# inktime_schematic.net
KiCad netlist of a schematic drawn in EAGLE
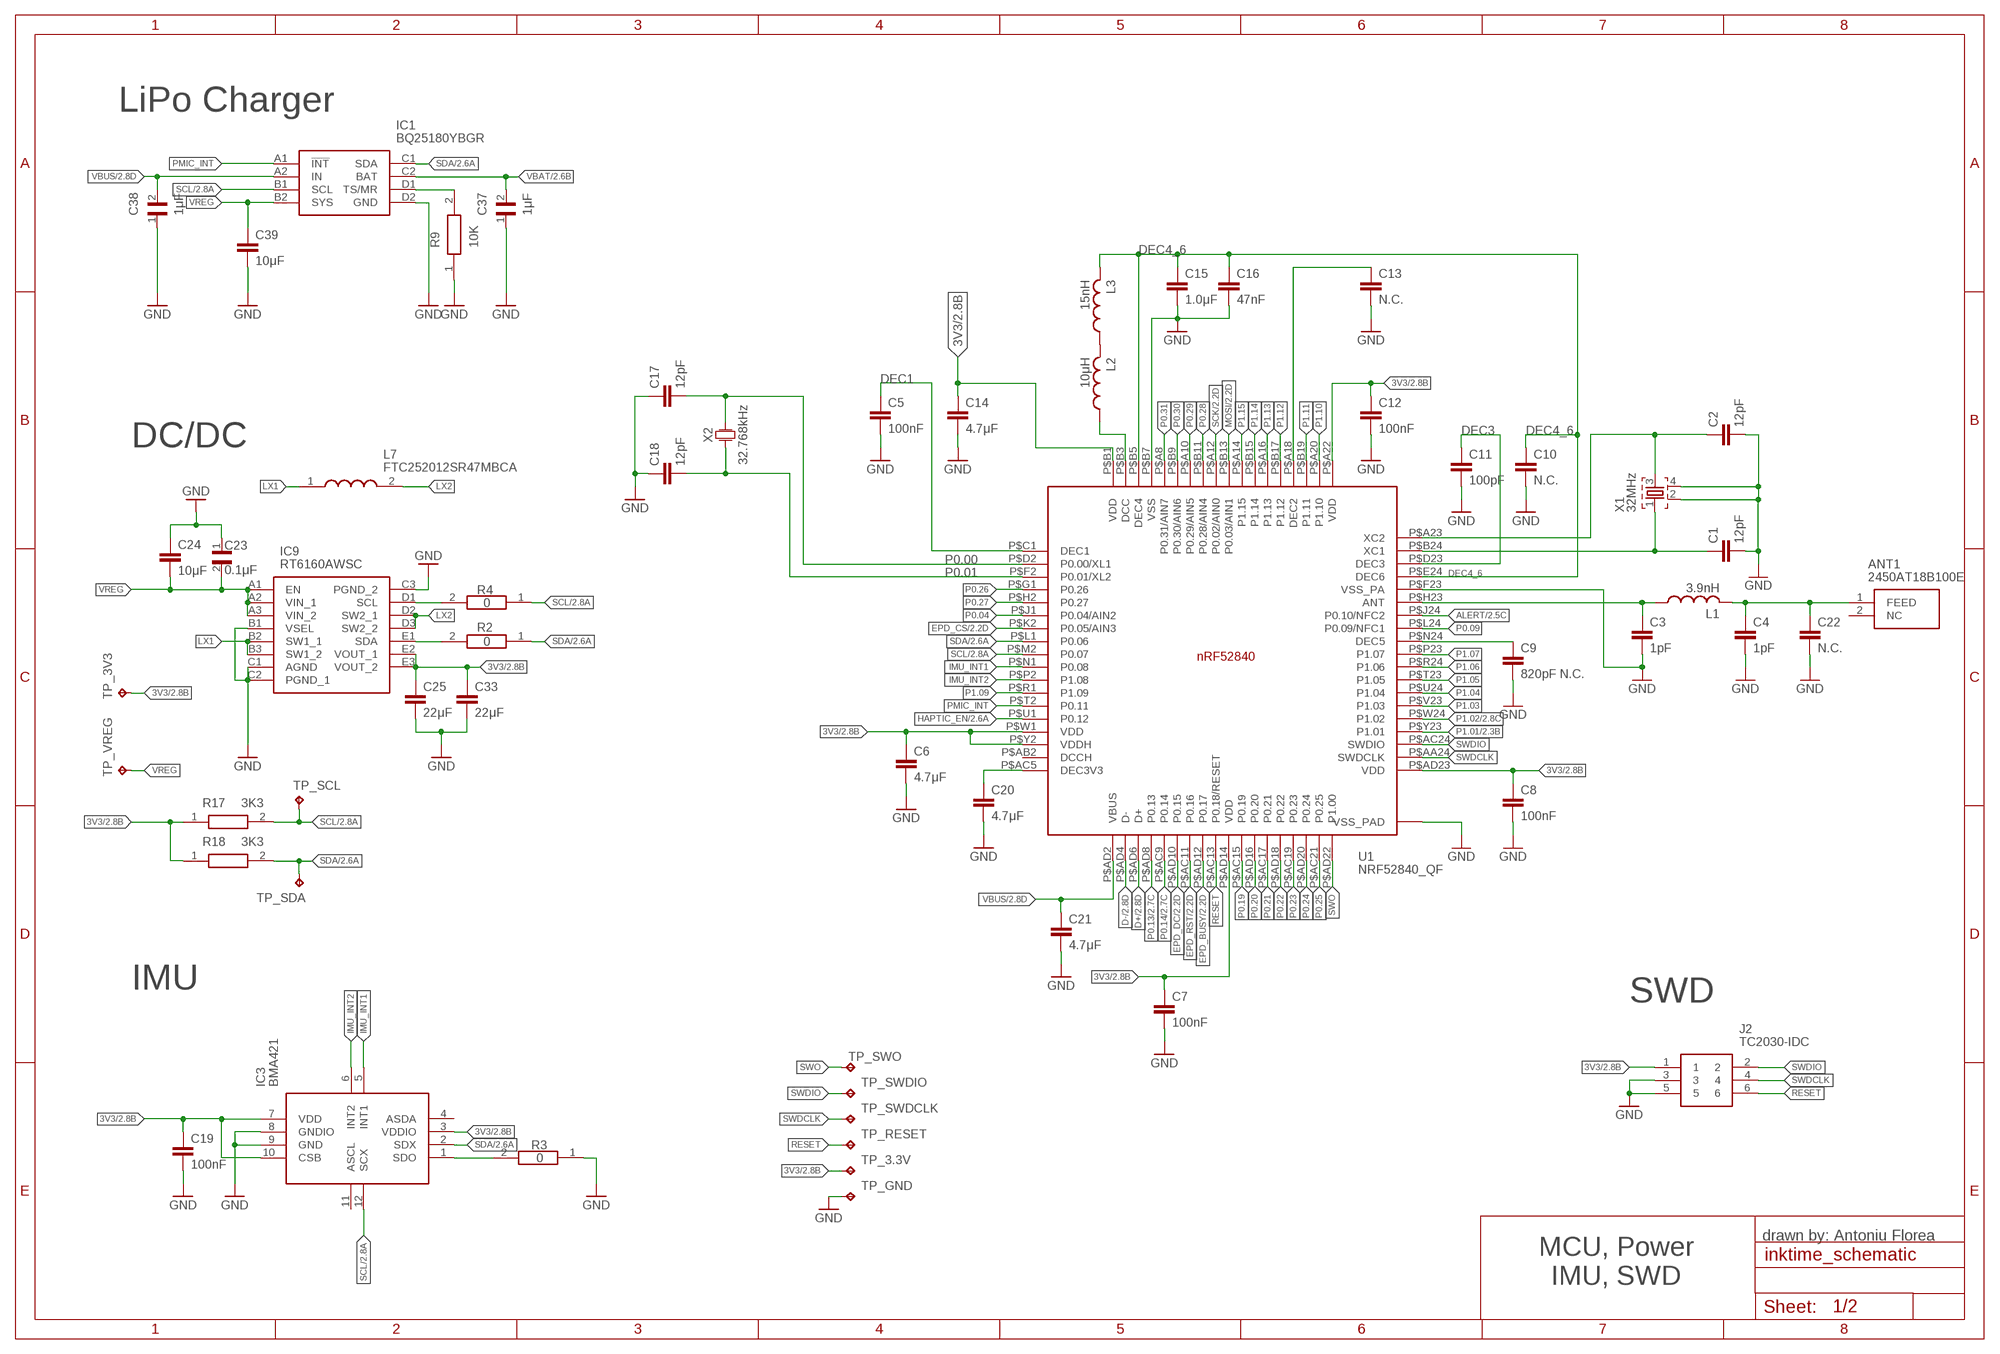
[diagram p0: schematic, sheet 1]
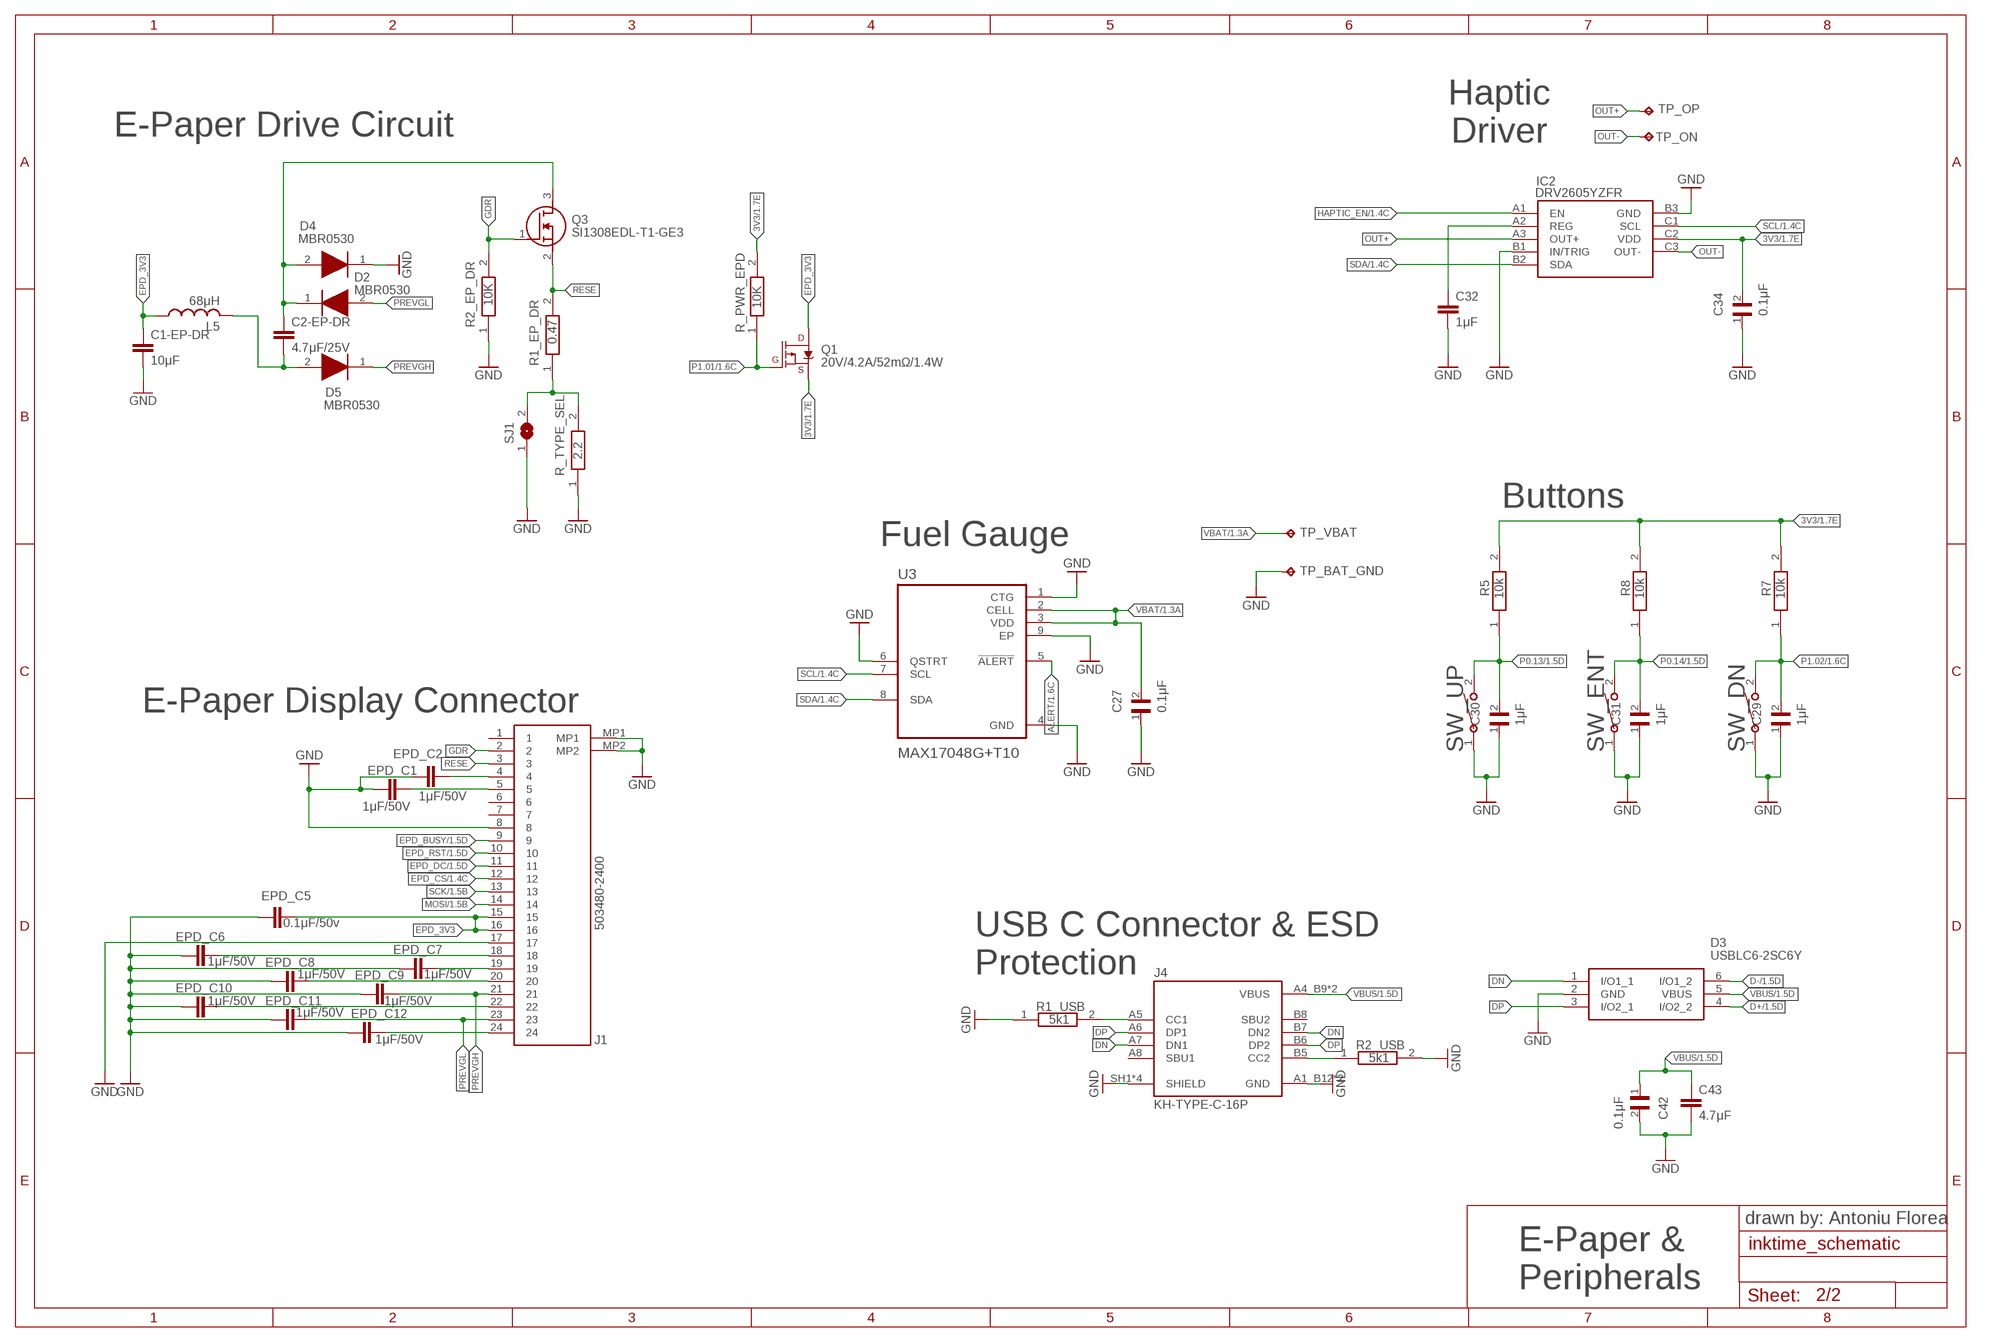
[diagram p1: schematic, sheet 2]

(export (version "E")
  (design (tool "Eeschema 10.0.6"))
  (components
    (comp (ref "C1-EP-DR")
      (value "10μF")
      (footprint "eagle-import:NORDIC_NRF_3_RESC0402_L")
      (libsource (lib "eagle-import") (part "NORDIC_NRF_3_CAPACITOR_0402_L"))
    )
    (comp (ref "C2-EP-DR")
      (value "4.7μF/25V")
      (footprint "eagle-import:NORDIC_NRF_3_RESC0402_L")
      (libsource (lib "eagle-import") (part "NORDIC_NRF_3_CAPACITOR_0402_L"))
    )
    (comp (ref "C27")
      (value "0.1μF")
      (footprint "eagle-import:GRM011R60J152KE01L_2_CAPC0201X13N")
      (fields (field (name "MF") "Murata") (field (name "MP") "GRM011R60J152KE01L"))
      (libsource (lib "eagle-import") (part "GRM011R60J152KE01L_2_GRM011R60J152KE01L"))
    )
    (comp (ref "C29")
      (value "1μF")
      (footprint "eagle-import:GRM011R60J152KE01L_2_CAPC0201X13N")
      (fields (field (name "MF") "Murata") (field (name "MP") "GRM011R60J152KE01L"))
      (libsource (lib "eagle-import") (part "GRM011R60J152KE01L_2_GRM011R60J152KE01L"))
    )
    (comp (ref "C30")
      (value "1μF")
      (footprint "eagle-import:GRM011R60J152KE01L_2_CAPC0201X13N")
      (fields (field (name "MF") "Murata") (field (name "MP") "GRM011R60J152KE01L"))
      (libsource (lib "eagle-import") (part "GRM011R60J152KE01L_2_GRM011R60J152KE01L"))
    )
    (comp (ref "C31")
      (value "1μF")
      (footprint "eagle-import:GRM011R60J152KE01L_2_CAPC0201X13N")
      (fields (field (name "MF") "Murata") (field (name "MP") "GRM011R60J152KE01L"))
      (libsource (lib "eagle-import") (part "GRM011R60J152KE01L_2_GRM011R60J152KE01L"))
    )
    (comp (ref "C32")
      (value "1μF")
      (footprint "eagle-import:NORDIC_NRF_3_RESC0402_L")
      (libsource (lib "eagle-import") (part "NORDIC_NRF_3_CAPACITOR_0402_L"))
    )
    (comp (ref "C34")
      (value "0.1μF")
      (footprint "eagle-import:GRM011R60J152KE01L_2_CAPC0201X13N")
      (fields (field (name "MF") "Murata") (field (name "MP") "GRM011R60J152KE01L"))
      (libsource (lib "eagle-import") (part "GRM011R60J152KE01L_2_GRM011R60J152KE01L"))
    )
    (comp (ref "C42")
      (value "0.1μF")
      (footprint "eagle-import:GRM011R60J152KE01L_2_CAPC0201X13N")
      (fields (field (name "MF") "Murata") (field (name "MP") "GRM011R60J152KE01L"))
      (libsource (lib "eagle-import") (part "GRM011R60J152KE01L_2_GRM011R60J152KE01L"))
    )
    (comp (ref "C43")
      (value "4.7μF")
      (footprint "eagle-import:NORDIC_NRF_3_RESC0402_L")
      (libsource (lib "eagle-import") (part "NORDIC_NRF_3_CAPACITOR_0402_L"))
    )
    (comp (ref "D2")
      (value "MBR0530")
      (footprint "eagle-import:ESP32_C6_LIBRARY_5_SOD3716X135N")
      (fields (field (name "MF") "ON Semiconductor"))
      (libsource (lib "eagle-import") (part "ESP32_C6_LIBRARY_5_MBR0530"))
    )
    (comp (ref "D3")
      (value "USBLC6-2SC6Y")
      (footprint "eagle-import:ESP32_C6_LIBRARY_3_SOT95P280X145-6N")
      (fields (field (name "MF") "STMicroelectronics"))
      (libsource (lib "eagle-import") (part "ESP32_C6_LIBRARY_3_USBLC6-2SC6Y"))
    )
    (comp (ref "D4")
      (value "MBR0530")
      (footprint "eagle-import:ESP32_C6_LIBRARY_5_SOD3716X135N")
      (fields (field (name "MF") "ON Semiconductor"))
      (libsource (lib "eagle-import") (part "ESP32_C6_LIBRARY_5_MBR0530"))
    )
    (comp (ref "D5")
      (value "MBR0530")
      (footprint "eagle-import:ESP32_C6_LIBRARY_5_SOD3716X135N")
      (fields (field (name "MF") "ON Semiconductor"))
      (libsource (lib "eagle-import") (part "ESP32_C6_LIBRARY_5_MBR0530"))
    )
    (comp (ref "EPD_C1")
      (value "1μF/50V")
      (footprint "eagle-import:NORDIC_NRF_3_RESC0402_L")
      (libsource (lib "eagle-import") (part "NORDIC_NRF_3_CAPACITOR_0402_L"))
    )
    (comp (ref "EPD_C2")
      (value "1μF/50V")
      (footprint "eagle-import:NORDIC_NRF_3_RESC0402_L")
      (libsource (lib "eagle-import") (part "NORDIC_NRF_3_CAPACITOR_0402_L"))
    )
    (comp (ref "EPD_C5")
      (value "0.1μF/50v")
      (footprint "eagle-import:NORDIC_NRF_3_RESC0201_L")
      (libsource (lib "eagle-import") (part "NORDIC_NRF_3_CAPACITOR_0201_L"))
    )
    (comp (ref "EPD_C6")
      (value "1μF/50V")
      (footprint "eagle-import:NORDIC_NRF_3_RESC0402_L")
      (libsource (lib "eagle-import") (part "NORDIC_NRF_3_CAPACITOR_0402_L"))
    )
    (comp (ref "EPD_C7")
      (value "1μF/50V")
      (footprint "eagle-import:NORDIC_NRF_3_RESC0402_L")
      (libsource (lib "eagle-import") (part "NORDIC_NRF_3_CAPACITOR_0402_L"))
    )
    (comp (ref "EPD_C8")
      (value "1μF/50V")
      (footprint "eagle-import:NORDIC_NRF_3_RESC0402_L")
      (libsource (lib "eagle-import") (part "NORDIC_NRF_3_CAPACITOR_0402_L"))
    )
    (comp (ref "EPD_C9")
      (value "1μF/50V")
      (footprint "eagle-import:NORDIC_NRF_3_RESC0402_L")
      (libsource (lib "eagle-import") (part "NORDIC_NRF_3_CAPACITOR_0402_L"))
    )
    (comp (ref "EPD_C10")
      (value "1μF/50V")
      (footprint "eagle-import:NORDIC_NRF_3_RESC0402_L")
      (libsource (lib "eagle-import") (part "NORDIC_NRF_3_CAPACITOR_0402_L"))
    )
    (comp (ref "EPD_C11")
      (value "1μF/50V")
      (footprint "eagle-import:NORDIC_NRF_3_RESC0402_L")
      (libsource (lib "eagle-import") (part "NORDIC_NRF_3_CAPACITOR_0402_L"))
    )
    (comp (ref "EPD_C12")
      (value "1μF/50V")
      (footprint "eagle-import:NORDIC_NRF_3_RESC0402_L")
      (libsource (lib "eagle-import") (part "NORDIC_NRF_3_CAPACITOR_0402_L"))
    )
    (comp (ref "IC2")
      (value "DRV2605YZFR")
      (footprint "eagle-import:DRV2605YZFR_BGA9C50P3X3_144X144X62")
      (libsource (lib "eagle-import") (part "DRV2605YZFR_DRV2605YZFR"))
    )
    (comp (ref "J1")
      (value "503480-2400")
      (footprint "eagle-import:503480-2400_5034802400")
      (fields (field (name "MOUSER_PART_NUMBER") "538-503480-2400"))
      (libsource (lib "eagle-import") (part "503480-2400_503480-2400"))
    )
    (comp (ref "J4")
      (value "KH-TYPE-C-16P")
      (footprint "eagle-import:KH-TYPE-C-16P_KINGHELM_KH-TYPE-C-16P")
      (fields (field (name "MF") "kinghelm"))
      (libsource (lib "eagle-import") (part "KH-TYPE-C-16P_KH-TYPE-C-16P"))
    )
    (comp (ref "L5")
      (value "68μH")
      (footprint "eagle-import:NORDIC_NRF_2_RESC0402_L")
      (libsource (lib "eagle-import") (part "NORDIC_NRF_2_INDUCTOR_0402_L"))
    )
    (comp (ref "Q1")
      (value "20V/4.2A/52mΩ/1.4W")
      (footprint "eagle-import:ESP32_C6_LIBRARY_4_ESP32_C6_LIBRARY_4_ESP32_C6_LIBRARY_4_ESP32_C6_LIBRARY_4_ESP32_WROVER_SPARKFUN-DISCRETESEMI_SOT23-3")
      (libsource (lib "eagle-import") (part "ESP32_C6_LIBRARY_4_ESP32_WROVER_SPARKFUN-DISCRETESEMI_MOSFET_PCH-DMG2305UX-7"))
    )
    (comp (ref "Q3")
      (value "SI1308EDL-T1-GE3")
      (footprint "eagle-import:ESP32_C6_LIBRARY_6_SOT65P210X110-3N")
      (fields (field (name "MF") "Vishay Siliconix"))
      (libsource (lib "eagle-import") (part "ESP32_C6_LIBRARY_6_SI1308EDL-T1-GE3"))
    )
    (comp (ref "R1_EP_DR")
      (value "0.47")
      (footprint "eagle-import:CPF0201D7K68C1_0201")
      (libsource (lib "eagle-import") (part "CPF0201D7K68C1_CPF0201D7K68C1"))
    )
    (comp (ref "R1_USB")
      (value "5k1")
      (footprint "eagle-import:ERA-1AEB3401C_0201")
      (libsource (lib "eagle-import") (part "ERA-1AEB3401C_CPF0201D7K68C1"))
    )
    (comp (ref "R2_EP_DR")
      (value "10K")
      (footprint "eagle-import:CPF0201D7K68C1_0201")
      (libsource (lib "eagle-import") (part "CPF0201D7K68C1_CPF0201D7K68C1"))
    )
    (comp (ref "R2_USB")
      (value "5k1")
      (footprint "eagle-import:ERA-1AEB3401C_0201")
      (libsource (lib "eagle-import") (part "ERA-1AEB3401C_CPF0201D7K68C1"))
    )
    (comp (ref "R5")
      (value "10k")
      (footprint "eagle-import:CPF0201D7K68C1_0201")
      (libsource (lib "eagle-import") (part "CPF0201D7K68C1_CPF0201D7K68C1"))
    )
    (comp (ref "R7")
      (value "10k")
      (footprint "eagle-import:CPF0201D7K68C1_0201")
      (libsource (lib "eagle-import") (part "CPF0201D7K68C1_CPF0201D7K68C1"))
    )
    (comp (ref "R8")
      (value "10k")
      (footprint "eagle-import:CPF0201D7K68C1_0201")
      (libsource (lib "eagle-import") (part "CPF0201D7K68C1_CPF0201D7K68C1"))
    )
    (comp (ref "R_PWR_EPD")
      (value "10K")
      (footprint "eagle-import:CPF0201D7K68C1_0201")
      (libsource (lib "eagle-import") (part "CPF0201D7K68C1_CPF0201D7K68C1"))
    )
    (comp (ref "R_TYPE_SEL")
      (value "2.2")
      (footprint "eagle-import:CPF0201D7K68C1_0201")
      (libsource (lib "eagle-import") (part "CPF0201D7K68C1_CPF0201D7K68C1"))
    )
    (comp (ref "SJ1")
      (value "ESP32_C6_LIBRARY_7_JUMPER_SJ")
      (footprint "eagle-import:ESP32_C6_LIBRARY_7_JUMPER_SJ")
      (libsource (lib "eagle-import") (part "ESP32_C6_LIBRARY_7_JUMPER_SJ"))
    )
    (comp (ref "SW_DN")
      (value "2025-10-22_07-23-44_LIBRARY_EVP-AKE31ASW_EVP-AKE31A_PAN")
      (footprint "eagle-import:2025-10-22_07-23-44_LIBRARY_SW_EVP-AKE31A_PAN")
      (fields
        (field (name "MANUFACTURER_PART_NUMBER") "EVP-AKE31A")
        (field (name "COPYRIGHT") "Copyright (C) 2025 Ultra Librarian. All rights reserved.")
      )
      (libsource (lib "eagle-import") (part "2025-10-22_07-23-44_LIBRARY_EVP-AKE31ASW_EVP-AKE31A_PAN"))
    )
    (comp (ref "SW_ENT")
      (value "2025-10-22_07-23-44_LIBRARY_EVP-AKE31ASW_EVP-AKE31A_PAN")
      (footprint "eagle-import:2025-10-22_07-23-44_LIBRARY_SW_EVP-AKE31A_PAN")
      (fields
        (field (name "MANUFACTURER_PART_NUMBER") "EVP-AKE31A")
        (field (name "COPYRIGHT") "Copyright (C) 2025 Ultra Librarian. All rights reserved.")
      )
      (libsource (lib "eagle-import") (part "2025-10-22_07-23-44_LIBRARY_EVP-AKE31ASW_EVP-AKE31A_PAN"))
    )
    (comp (ref "SW_UP")
      (value "2025-10-22_07-23-44_LIBRARY_EVP-AKE31ASW_EVP-AKE31A_PAN")
      (footprint "eagle-import:2025-10-22_07-23-44_LIBRARY_SW_EVP-AKE31A_PAN")
      (fields
        (field (name "MANUFACTURER_PART_NUMBER") "EVP-AKE31A")
        (field (name "COPYRIGHT") "Copyright (C) 2025 Ultra Librarian. All rights reserved.")
      )
      (libsource (lib "eagle-import") (part "2025-10-22_07-23-44_LIBRARY_EVP-AKE31ASW_EVP-AKE31A_PAN"))
    )
    (comp (ref "TP_BAT_GND")
      (value "HECTOR_WATCH_1_TPTP20R")
      (footprint "eagle-import:HECTOR_WATCH_1_TP20R")
      (libsource (lib "eagle-import") (part "HECTOR_WATCH_1_TPTP20R"))
    )
    (comp (ref "TP_ON")
      (value "HECTOR_WATCH_1_TPTP20R")
      (footprint "eagle-import:HECTOR_WATCH_1_TP20R")
      (libsource (lib "eagle-import") (part "HECTOR_WATCH_1_TPTP20R"))
    )
    (comp (ref "TP_OP")
      (value "HECTOR_WATCH_1_TPTP20R")
      (footprint "eagle-import:HECTOR_WATCH_1_TP20R")
      (libsource (lib "eagle-import") (part "HECTOR_WATCH_1_TPTP20R"))
    )
    (comp (ref "TP_VBAT")
      (value "HECTOR_WATCH_1_TPTP20R")
      (footprint "eagle-import:HECTOR_WATCH_1_TP20R")
      (libsource (lib "eagle-import") (part "HECTOR_WATCH_1_TPTP20R"))
    )
    (comp (ref "U3")
      (value "MAX17048G+T10")
      (footprint "eagle-import:ESP32_C6_LIBRARY_SON50P200X200X80-9N")
      (fields (field (name "MF") "Analog Devices"))
      (libsource (lib "eagle-import") (part "ESP32_C6_LIBRARY_MAX17048G+T10"))
    )
    (comp (ref "ANT1")
      (value "2450AT18B100E")
      (footprint "eagle-import:2450AT18B100E_ANTC3216X140N")
      (fields (field (name "MOUSER_PART_NUMBER") "609-2450AT18B100E"))
      (libsource (lib "eagle-import") (part "2450AT18B100E_2450AT18B100E"))
    )
    (comp (ref "C1")
      (value "12pF")
      (footprint "eagle-import:NORDIC_NRF_3_RESC0201_L")
      (libsource (lib "eagle-import") (part "NORDIC_NRF_3_CAPACITOR_0201_L"))
    )
    (comp (ref "C2")
      (value "12pF")
      (footprint "eagle-import:NORDIC_NRF_3_RESC0201_L")
      (libsource (lib "eagle-import") (part "NORDIC_NRF_3_CAPACITOR_0201_L"))
    )
    (comp (ref "C3")
      (value "1pF")
      (footprint "eagle-import:NORDIC_NRF_3_RESC0201_L")
      (libsource (lib "eagle-import") (part "NORDIC_NRF_3_CAPACITOR_0201_L"))
    )
    (comp (ref "C4")
      (value "1pF")
      (footprint "eagle-import:NORDIC_NRF_3_RESC0201_L")
      (libsource (lib "eagle-import") (part "NORDIC_NRF_3_CAPACITOR_0201_L"))
    )
    (comp (ref "C5")
      (value "100nF")
      (footprint "eagle-import:NORDIC_NRF_3_RESC0201_L")
      (libsource (lib "eagle-import") (part "NORDIC_NRF_3_CAPACITOR_0201_L"))
    )
    (comp (ref "C6")
      (value "4.7μF")
      (footprint "eagle-import:NORDIC_NRF_3_RESC0402_L")
      (libsource (lib "eagle-import") (part "NORDIC_NRF_3_CAPACITOR_0402_L"))
    )
    (comp (ref "C7")
      (value "100nF")
      (footprint "eagle-import:NORDIC_NRF_3_RESC0201_L")
      (libsource (lib "eagle-import") (part "NORDIC_NRF_3_CAPACITOR_0201_L"))
    )
    (comp (ref "C8")
      (value "100nF")
      (footprint "eagle-import:NORDIC_NRF_3_RESC0201_L")
      (libsource (lib "eagle-import") (part "NORDIC_NRF_3_CAPACITOR_0201_L"))
    )
    (comp (ref "C9")
      (value "820pF N.C.")
      (footprint "eagle-import:NORDIC_NRF_3_RESC0201_L")
      (libsource (lib "eagle-import") (part "NORDIC_NRF_3_CAPACITOR_0201_L"))
    )
    (comp (ref "C10")
      (value "N.C.")
      (footprint "eagle-import:NORDIC_NRF_3_RESC0201_L")
      (libsource (lib "eagle-import") (part "NORDIC_NRF_3_CAPACITOR_0201_L"))
    )
    (comp (ref "C11")
      (value "100pF")
      (footprint "eagle-import:NORDIC_NRF_3_RESC0201_L")
      (libsource (lib "eagle-import") (part "NORDIC_NRF_3_CAPACITOR_0201_L"))
    )
    (comp (ref "C12")
      (value "100nF")
      (footprint "eagle-import:NORDIC_NRF_3_RESC0201_L")
      (libsource (lib "eagle-import") (part "NORDIC_NRF_3_CAPACITOR_0201_L"))
    )
    (comp (ref "C13")
      (value "N.C.")
      (footprint "eagle-import:NORDIC_NRF_3_RESC0201_L")
      (libsource (lib "eagle-import") (part "NORDIC_NRF_3_CAPACITOR_0201_L"))
    )
    (comp (ref "C14")
      (value "4.7μF")
      (footprint "eagle-import:NORDIC_NRF_3_RESC0402_L")
      (libsource (lib "eagle-import") (part "NORDIC_NRF_3_CAPACITOR_0402_L"))
    )
    (comp (ref "C15")
      (value "1.0μF")
      (footprint "eagle-import:NORDIC_NRF_3_RESC0402_L")
      (libsource (lib "eagle-import") (part "NORDIC_NRF_3_CAPACITOR_0402_L"))
    )
    (comp (ref "C16")
      (value "47nF")
      (footprint "eagle-import:NORDIC_NRF_3_RESC0201_L")
      (libsource (lib "eagle-import") (part "NORDIC_NRF_3_CAPACITOR_0201_L"))
    )
    (comp (ref "C17")
      (value "12pF")
      (footprint "eagle-import:NORDIC_NRF_3_RESC0201_L")
      (libsource (lib "eagle-import") (part "NORDIC_NRF_3_CAPACITOR_0201_L"))
    )
    (comp (ref "C18")
      (value "12pF")
      (footprint "eagle-import:NORDIC_NRF_3_RESC0201_L")
      (libsource (lib "eagle-import") (part "NORDIC_NRF_3_CAPACITOR_0201_L"))
    )
    (comp (ref "C19")
      (value "100nF")
      (footprint "eagle-import:NORDIC_NRF_3_RESC0201_L")
      (libsource (lib "eagle-import") (part "NORDIC_NRF_3_CAPACITOR_0201_L"))
    )
    (comp (ref "C20")
      (value "4.7μF")
      (footprint "eagle-import:NORDIC_NRF_3_RESC0402_L")
      (libsource (lib "eagle-import") (part "NORDIC_NRF_3_CAPACITOR_0402_L"))
    )
    (comp (ref "C21")
      (value "4.7μF")
      (footprint "eagle-import:NORDIC_NRF_3_RESC0402_L")
      (libsource (lib "eagle-import") (part "NORDIC_NRF_3_CAPACITOR_0402_L"))
    )
    (comp (ref "C22")
      (value "N.C.")
      (footprint "eagle-import:NORDIC_NRF_3_RESC0201_L")
      (libsource (lib "eagle-import") (part "NORDIC_NRF_3_CAPACITOR_0201_L"))
    )
    (comp (ref "C23")
      (value "0.1μF")
      (footprint "eagle-import:GRM011R60J152KE01L_2_CAPC0201X13N")
      (fields (field (name "MF") "Murata") (field (name "MP") "GRM011R60J152KE01L"))
      (libsource (lib "eagle-import") (part "GRM011R60J152KE01L_2_GRM011R60J152KE01L"))
    )
    (comp (ref "C24")
      (value "10μF")
      (footprint "eagle-import:NORDIC_NRF_3_RESC0402_L")
      (libsource (lib "eagle-import") (part "NORDIC_NRF_3_CAPACITOR_0402_L"))
    )
    (comp (ref "C25")
      (value "22μF")
      (footprint "eagle-import:NORDIC_NRF_3_RESC0402_L")
      (libsource (lib "eagle-import") (part "NORDIC_NRF_3_CAPACITOR_0402_L"))
    )
    (comp (ref "C33")
      (value "22μF")
      (footprint "eagle-import:NORDIC_NRF_3_RESC0402_L")
      (libsource (lib "eagle-import") (part "NORDIC_NRF_3_CAPACITOR_0402_L"))
    )
    (comp (ref "C37")
      (value "1μF")
      (footprint "eagle-import:GRM011R60J152KE01L_2_CAPC0201X13N")
      (fields (field (name "MF") "Murata") (field (name "MP") "GRM011R60J152KE01L"))
      (libsource (lib "eagle-import") (part "GRM011R60J152KE01L_2_GRM011R60J152KE01L"))
    )
    (comp (ref "C38")
      (value "1μF")
      (footprint "eagle-import:GRM011R60J152KE01L_2_CAPC0201X13N")
      (fields (field (name "MF") "Murata") (field (name "MP") "GRM011R60J152KE01L"))
      (libsource (lib "eagle-import") (part "GRM011R60J152KE01L_2_GRM011R60J152KE01L"))
    )
    (comp (ref "C39")
      (value "10μF")
      (footprint "eagle-import:NORDIC_NRF_3_RESC0402_L")
      (libsource (lib "eagle-import") (part "NORDIC_NRF_3_CAPACITOR_0402_L"))
    )
    (comp (ref "IC1")
      (value "BQ25180YBGR")
      (footprint "eagle-import:BQ25180YBGR_BGA8C40P2X4_100X155X50")
      (fields (field (name "MOUSER_PART_NUMBER") "595-BQ25180YBGR"))
      (libsource (lib "eagle-import") (part "BQ25180YBGR_BQ25180YBGR"))
    )
    (comp (ref "IC3")
      (value "BMA421")
      (footprint "eagle-import:BMA423_BMA423")
      (fields (field (name "ARROW_PART_NUMBER") "BMA423") (field (name "MOUSER_PART_NUMBER") "262-BMA423"))
      (libsource (lib "eagle-import") (part "BMA423_BMA423"))
    )
    (comp (ref "IC9")
      (value "RT6160AWSC")
      (footprint "eagle-import:RT6160AWSC_BGA15C40P3X5_140X230X60")
      (fields (field (name "MOUSER_PART_NUMBER") "835-RT6160AWSC"))
      (libsource (lib "eagle-import") (part "RT6160AWSC_RT6160AWSC"))
    )
    (comp (ref "J2")
      (value "TC2030-IDC")
      (footprint "eagle-import:TC2030-IDC_TC2030IDC")
      (libsource (lib "eagle-import") (part "TC2030-IDC_TC2030-IDC"))
    )
    (comp (ref "L1")
      (value "3.9nH")
      (footprint "eagle-import:NORDIC_NRF_2_RESC0201_L")
      (libsource (lib "eagle-import") (part "NORDIC_NRF_2_INDUCTOR_0201_L"))
    )
    (comp (ref "L2")
      (value "10μH")
      (footprint "eagle-import:NORDIC_NRF_2_RESC0201_L")
      (libsource (lib "eagle-import") (part "NORDIC_NRF_2_INDUCTOR_0201_L"))
    )
    (comp (ref "L3")
      (value "15nH")
      (footprint "eagle-import:NORDIC_NRF_2_RESC0201_L")
      (libsource (lib "eagle-import") (part "NORDIC_NRF_2_INDUCTOR_0201_L"))
    )
    (comp (ref "L7")
      (value "FTC252012SR47MBCA")
      (footprint "eagle-import:MLP2016SR47MT0S1_INDC2016X100N")
      (libsource (lib "eagle-import") (part "MLP2016SR47MT0S1_FTC252012SR47MBCA"))
    )
    (comp (ref "R2")
      (value "0")
      (footprint "eagle-import:CPF0201D7K68C1_0201")
      (libsource (lib "eagle-import") (part "CPF0201D7K68C1_CPF0201D7K68C1"))
    )
    (comp (ref "R3")
      (value "0")
      (footprint "eagle-import:CPF0201D7K68C1_0201")
      (libsource (lib "eagle-import") (part "CPF0201D7K68C1_CPF0201D7K68C1"))
    )
    (comp (ref "R4")
      (value "0")
      (footprint "eagle-import:CPF0201D7K68C1_0201")
      (libsource (lib "eagle-import") (part "CPF0201D7K68C1_CPF0201D7K68C1"))
    )
    (comp (ref "R9")
      (value "10K")
      (footprint "eagle-import:ERA-1AEB3401C_0201")
      (libsource (lib "eagle-import") (part "ERA-1AEB3401C_CPF0201D7K68C1"))
    )
    (comp (ref "R17")
      (value "3K3")
      (footprint "eagle-import:CPF0201D7K68C1_0201")
      (libsource (lib "eagle-import") (part "CPF0201D7K68C1_CPF0201D7K68C1"))
    )
    (comp (ref "R18")
      (value "3K3")
      (footprint "eagle-import:CPF0201D7K68C1_0201")
      (libsource (lib "eagle-import") (part "CPF0201D7K68C1_CPF0201D7K68C1"))
    )
    (comp (ref "TP_3.3V")
      (value "HECTOR_WATCH_1_TPTP20R")
      (footprint "eagle-import:HECTOR_WATCH_1_TP20R")
      (libsource (lib "eagle-import") (part "HECTOR_WATCH_1_TPTP20R"))
    )
    (comp (ref "TP_3V3")
      (value "HECTOR_WATCH_1_TPTP20R")
      (footprint "eagle-import:HECTOR_WATCH_1_TP20R")
      (libsource (lib "eagle-import") (part "HECTOR_WATCH_1_TPTP20R"))
    )
    (comp (ref "TP_GND")
      (value "HECTOR_WATCH_1_TPTP20R")
      (footprint "eagle-import:HECTOR_WATCH_1_TP20R")
      (libsource (lib "eagle-import") (part "HECTOR_WATCH_1_TPTP20R"))
    )
    (comp (ref "TP_RESET")
      (value "HECTOR_WATCH_1_TPTP20R")
      (footprint "eagle-import:HECTOR_WATCH_1_TP20R")
      (libsource (lib "eagle-import") (part "HECTOR_WATCH_1_TPTP20R"))
    )
    (comp (ref "TP_SCL")
      (value "HECTOR_WATCH_1_TPTP20R")
      (footprint "eagle-import:HECTOR_WATCH_1_TP20R")
      (libsource (lib "eagle-import") (part "HECTOR_WATCH_1_TPTP20R"))
    )
    (comp (ref "TP_SDA")
      (value "HECTOR_WATCH_1_TPTP20R")
      (footprint "eagle-import:HECTOR_WATCH_1_TP20R")
      (libsource (lib "eagle-import") (part "HECTOR_WATCH_1_TPTP20R"))
    )
    (comp (ref "TP_SWDCLK")
      (value "HECTOR_WATCH_1_TPTP20R")
      (footprint "eagle-import:HECTOR_WATCH_1_TP20R")
      (libsource (lib "eagle-import") (part "HECTOR_WATCH_1_TPTP20R"))
    )
    (comp (ref "TP_SWDIO")
      (value "HECTOR_WATCH_1_TPTP20R")
      (footprint "eagle-import:HECTOR_WATCH_1_TP20R")
      (libsource (lib "eagle-import") (part "HECTOR_WATCH_1_TPTP20R"))
    )
    (comp (ref "TP_SWO")
      (value "HECTOR_WATCH_1_TPTP20R")
      (footprint "eagle-import:HECTOR_WATCH_1_TP20R")
      (libsource (lib "eagle-import") (part "HECTOR_WATCH_1_TPTP20R"))
    )
    (comp (ref "TP_VREG")
      (value "HECTOR_WATCH_1_TPTP20R")
      (footprint "eagle-import:HECTOR_WATCH_1_TP20R")
      (libsource (lib "eagle-import") (part "HECTOR_WATCH_1_TPTP20R"))
    )
    (comp (ref "U1")
      (value "NRF52840_QF")
      (footprint "eagle-import:NORDIC_NRF_4_AQFN50P700X700X85_HS-74N")
      (libsource (lib "eagle-import") (part "NORDIC_NRF_4_NRF52840_QF"))
    )
    (comp (ref "X1")
      (value "32MHz")
      (footprint "eagle-import:NORDIC_NRF_BT-XTAL_2016_N")
      (libsource (lib "eagle-import") (part "NORDIC_NRF_XTAL_32MHZ"))
    )
    (comp (ref "X2")
      (value "32.768kHz")
      (footprint "eagle-import:XTAL330X1051X90N")
      (fields
        (field (name "MANUFACTURER") "EPSON")
        (field (name "MPN") "FC-135 32.7680KA-A5")
        (field (name "TOLERANCE") "±20 ppm")
      )
      (libsource (lib "eagle-import") (part "FC-135"))
    )
  )
  (nets
    (net (code "1") (name "3V3") (class "Default")
      (node (ref "C12") (pin "1") (pinfunction "1_1") (pintype "passive"))
      (node (ref "C14") (pin "1") (pinfunction "1_1") (pintype "passive"))
      (node (ref "C19") (pin "1") (pinfunction "1_1") (pintype "passive"))
      (node (ref "C25") (pin "1") (pinfunction "1_1") (pintype "passive"))
      (node (ref "C33") (pin "1") (pinfunction "1_1") (pintype "passive"))
      (node (ref "C34") (pin "2") (pinfunction "2_2") (pintype "passive"))
      (node (ref "C6") (pin "1") (pinfunction "1_1") (pintype "passive"))
      (node (ref "C7") (pin "1") (pinfunction "1_1") (pintype "passive"))
      (node (ref "C8") (pin "1") (pinfunction "1_1") (pintype "passive"))
      (node (ref "IC2") (pin "C2") (pinfunction "VDD_C2") (pintype "bidirectional"))
      (node (ref "IC3") (pin "10") (pinfunction "CSB_10") (pintype "bidirectional"))
      (node (ref "IC3") (pin "3") (pinfunction "VDDIO_3") (pintype "bidirectional"))
      (node (ref "IC3") (pin "7") (pinfunction "VDD_7") (pintype "bidirectional"))
      (node (ref "IC9") (pin "E2") (pinfunction "VOUT_1_E2") (pintype "bidirectional"))
      (node (ref "IC9") (pin "E3") (pinfunction "VOUT_2_E3") (pintype "bidirectional"))
      (node (ref "J2") (pin "1") (pinfunction "1_1") (pintype "bidirectional"))
      (node (ref "Q1") (pin "2") (pinfunction "S_2") (pintype "bidirectional"))
      (node (ref "R17") (pin "1") (pinfunction "1_1") (pintype "bidirectional"))
      (node (ref "R18") (pin "1") (pinfunction "1_1") (pintype "bidirectional"))
      (node (ref "R5") (pin "2") (pinfunction "2_2") (pintype "bidirectional"))
      (node (ref "R7") (pin "2") (pinfunction "2_2") (pintype "bidirectional"))
      (node (ref "R8") (pin "2") (pinfunction "2_2") (pintype "bidirectional"))
      (node (ref "R_PWR_EPD") (pin "2") (pinfunction "2_2") (pintype "bidirectional"))
      (node (ref "TP_3.3V") (pin "TP") (pinfunction "TP_TP") (pintype "input"))
      (node (ref "TP_3V3") (pin "TP") (pinfunction "TP_TP") (pintype "input"))
      (node (ref "U1") (pin "P$A22") (pinfunction "VDD_P$A22") (pintype "power_in"))
      (node (ref "U1") (pin "P$AD14") (pinfunction "VDD_P$AD14") (pintype "power_in"))
      (node (ref "U1") (pin "P$AD23") (pinfunction "VDD_P$AD23") (pintype "power_in"))
      (node (ref "U1") (pin "P$B1") (pinfunction "VDD_P$B1") (pintype "power_in"))
      (node (ref "U1") (pin "P$W1") (pinfunction "VDD_P$W1") (pintype "power_in"))
      (node (ref "U1") (pin "P$Y2") (pinfunction "VDDH_P$Y2") (pintype "power_in"))
    )
    (net (code "2") (name "ALERT") (class "Default")
      (node (ref "U1") (pin "P$J24") (pinfunction "P0.10/NFC2_P$J24") (pintype "bidirectional"))
      (node (ref "U3") (pin "5") (pinfunction "~{ALERT}_5") (pintype "output"))
    )
    (net (code "3") (name "D+") (class "Default")
      (node (ref "D3") (pin "4") (pinfunction "I/O2_2_4") (pintype "bidirectional"))
      (node (ref "U1") (pin "P$AD6") (pinfunction "D+_P$AD6") (pintype "bidirectional"))
    )
    (net (code "4") (name "D-") (class "Default")
      (node (ref "D3") (pin "6") (pinfunction "I/O1_2_6") (pintype "bidirectional"))
      (node (ref "U1") (pin "P$AD4") (pinfunction "D-_P$AD4") (pintype "bidirectional"))
    )
    (net (code "5") (name "DEC1") (class "Default")
      (node (ref "C5") (pin "1") (pinfunction "1_1") (pintype "passive"))
      (node (ref "U1") (pin "P$C1") (pinfunction "DEC1_P$C1") (pintype "power_in"))
    )
    (net (code "6") (name "DEC3") (class "Default")
      (node (ref "C11") (pin "1") (pinfunction "1_1") (pintype "passive"))
      (node (ref "U1") (pin "P$D23") (pinfunction "DEC3_P$D23") (pintype "bidirectional"))
    )
    (net (code "7") (name "DEC4_6") (class "Default")
      (node (ref "C10") (pin "1") (pinfunction "1_1") (pintype "passive"))
      (node (ref "C15") (pin "1") (pinfunction "1_1") (pintype "passive"))
      (node (ref "C16") (pin "1") (pinfunction "1_1") (pintype "passive"))
      (node (ref "L3") (pin "2") (pinfunction "2_2") (pintype "passive"))
      (node (ref "U1") (pin "P$B5") (pinfunction "DEC4_P$B5") (pintype "power_in"))
      (node (ref "U1") (pin "P$E24") (pinfunction "DEC6_P$E24") (pintype "bidirectional"))
    )
    (net (code "8") (name "DN") (class "Default")
      (node (ref "D3") (pin "1") (pinfunction "I/O1_1_1") (pintype "bidirectional"))
      (node (ref "J4") (pin "A7") (pinfunction "DN1_A7") (pintype "bidirectional"))
      (node (ref "J4") (pin "B7") (pinfunction "DN2_B7") (pintype "bidirectional"))
    )
    (net (code "9") (name "DP") (class "Default")
      (node (ref "D3") (pin "3") (pinfunction "I/O2_1_3") (pintype "bidirectional"))
      (node (ref "J4") (pin "A6") (pinfunction "DP1_A6") (pintype "bidirectional"))
      (node (ref "J4") (pin "B6") (pinfunction "DP2_B6") (pintype "bidirectional"))
    )
    (net (code "10") (name "EPD_3V3") (class "Default")
      (node (ref "C1-EP-DR") (pin "1") (pinfunction "1_1") (pintype "passive"))
      (node (ref "EPD_C5") (pin "2") (pinfunction "2_2") (pintype "passive"))
      (node (ref "J1") (pin "15") (pinfunction "15_15") (pintype "bidirectional"))
      (node (ref "J1") (pin "16") (pinfunction "16_16") (pintype "bidirectional"))
      (node (ref "L5") (pin "1") (pinfunction "1_1") (pintype "passive"))
      (node (ref "Q1") (pin "3") (pinfunction "D_3") (pintype "bidirectional"))
    )
    (net (code "11") (name "EPD_BUSY") (class "Default")
      (node (ref "J1") (pin "9") (pinfunction "9_9") (pintype "bidirectional"))
      (node (ref "U1") (pin "P$AD12") (pinfunction "P0.17_P$AD12") (pintype "bidirectional"))
    )
    (net (code "12") (name "EPD_CS") (class "Default")
      (node (ref "J1") (pin "12") (pinfunction "12_12") (pintype "bidirectional"))
      (node (ref "U1") (pin "P$K2") (pinfunction "P0.05/AIN3_P$K2") (pintype "bidirectional"))
    )
    (net (code "13") (name "EPD_DC") (class "Default")
      (node (ref "J1") (pin "11") (pinfunction "11_11") (pintype "bidirectional"))
      (node (ref "U1") (pin "P$AD10") (pinfunction "P0.15_P$AD10") (pintype "bidirectional"))
    )
    (net (code "14") (name "EPD_RST") (class "Default")
      (node (ref "J1") (pin "10") (pinfunction "10_10") (pintype "bidirectional"))
      (node (ref "U1") (pin "P$AC11") (pinfunction "P0.16_P$AC11") (pintype "bidirectional"))
    )
    (net (code "15") (name "GDR") (class "Default")
      (node (ref "J1") (pin "2") (pinfunction "2_2") (pintype "bidirectional"))
      (node (ref "Q3") (pin "1") (pinfunction "G_1") (pintype "bidirectional"))
      (node (ref "R2_EP_DR") (pin "2") (pinfunction "2_2") (pintype "bidirectional"))
    )
    (net (code "16") (name "GND") (class "Default")
      (node (ref "C1") (pin "2") (pinfunction "2_2") (pintype "passive"))
      (node (ref "C1-EP-DR") (pin "2") (pinfunction "2_2") (pintype "passive"))
      (node (ref "C10") (pin "2") (pinfunction "2_2") (pintype "passive"))
      (node (ref "C11") (pin "2") (pinfunction "2_2") (pintype "passive"))
      (node (ref "C12") (pin "2") (pinfunction "2_2") (pintype "passive"))
      (node (ref "C13") (pin "2") (pinfunction "2_2") (pintype "passive"))
      (node (ref "C14") (pin "2") (pinfunction "2_2") (pintype "passive"))
      (node (ref "C15") (pin "2") (pinfunction "2_2") (pintype "passive"))
      (node (ref "C16") (pin "2") (pinfunction "2_2") (pintype "passive"))
      (node (ref "C17") (pin "1") (pinfunction "1_1") (pintype "passive"))
      (node (ref "C18") (pin "1") (pinfunction "1_1") (pintype "passive"))
      (node (ref "C19") (pin "2") (pinfunction "2_2") (pintype "passive"))
      (node (ref "C2") (pin "2") (pinfunction "2_2") (pintype "passive"))
      (node (ref "C20") (pin "2") (pinfunction "2_2") (pintype "passive"))
      (node (ref "C21") (pin "2") (pinfunction "2_2") (pintype "passive"))
      (node (ref "C22") (pin "2") (pinfunction "2_2") (pintype "passive"))
      (node (ref "C23") (pin "1") (pinfunction "1_1") (pintype "passive"))
      (node (ref "C24") (pin "1") (pinfunction "1_1") (pintype "passive"))
      (node (ref "C25") (pin "2") (pinfunction "2_2") (pintype "passive"))
      (node (ref "C27") (pin "1") (pinfunction "1_1") (pintype "passive"))
      (node (ref "C29") (pin "1") (pinfunction "1_1") (pintype "passive"))
      (node (ref "C3") (pin "2") (pinfunction "2_2") (pintype "passive"))
      (node (ref "C30") (pin "1") (pinfunction "1_1") (pintype "passive"))
      (node (ref "C31") (pin "1") (pinfunction "1_1") (pintype "passive"))
      (node (ref "C32") (pin "2") (pinfunction "2_2") (pintype "passive"))
      (node (ref "C33") (pin "2") (pinfunction "2_2") (pintype "passive"))
      (node (ref "C34") (pin "1") (pinfunction "1_1") (pintype "passive"))
      (node (ref "C37") (pin "1") (pinfunction "1_1") (pintype "passive"))
      (node (ref "C38") (pin "1") (pinfunction "1_1") (pintype "passive"))
      (node (ref "C39") (pin "2") (pinfunction "2_2") (pintype "passive"))
      (node (ref "C4") (pin "2") (pinfunction "2_2") (pintype "passive"))
      (node (ref "C42") (pin "2") (pinfunction "2_2") (pintype "passive"))
      (node (ref "C43") (pin "2") (pinfunction "2_2") (pintype "passive"))
      (node (ref "C5") (pin "2") (pinfunction "2_2") (pintype "passive"))
      (node (ref "C6") (pin "2") (pinfunction "2_2") (pintype "passive"))
      (node (ref "C7") (pin "2") (pinfunction "2_2") (pintype "passive"))
      (node (ref "C8") (pin "2") (pinfunction "2_2") (pintype "passive"))
      (node (ref "C9") (pin "2") (pinfunction "2_2") (pintype "passive"))
      (node (ref "D3") (pin "2") (pinfunction "GND_2") (pintype "bidirectional"))
      (node (ref "D4") (pin "1") (pinfunction "K_1") (pintype "bidirectional"))
      (node (ref "EPD_C1") (pin "2") (pinfunction "2_2") (pintype "passive"))
      (node (ref "EPD_C10") (pin "2") (pinfunction "2_2") (pintype "passive"))
      (node (ref "EPD_C11") (pin "2") (pinfunction "2_2") (pintype "passive"))
      (node (ref "EPD_C12") (pin "2") (pinfunction "2_2") (pintype "passive"))
      (node (ref "EPD_C2") (pin "2") (pinfunction "2_2") (pintype "passive"))
      (node (ref "EPD_C5") (pin "1") (pinfunction "1_1") (pintype "passive"))
      (node (ref "EPD_C6") (pin "2") (pinfunction "2_2") (pintype "passive"))
      (node (ref "EPD_C7") (pin "2") (pinfunction "2_2") (pintype "passive"))
      (node (ref "EPD_C8") (pin "2") (pinfunction "2_2") (pintype "passive"))
      (node (ref "EPD_C9") (pin "2") (pinfunction "2_2") (pintype "passive"))
      (node (ref "IC1") (pin "D2") (pinfunction "GND_D2") (pintype "bidirectional"))
      (node (ref "IC2") (pin "B1") (pinfunction "IN/TRIG_B1") (pintype "bidirectional"))
      (node (ref "IC2") (pin "B3") (pinfunction "GND_B3") (pintype "bidirectional"))
      (node (ref "IC3") (pin "8") (pinfunction "GNDIO_8") (pintype "bidirectional"))
      (node (ref "IC3") (pin "9") (pinfunction "GND_9") (pintype "bidirectional"))
      (node (ref "IC9") (pin "B1") (pinfunction "VSEL_B1") (pintype "bidirectional"))
      (node (ref "IC9") (pin "C1") (pinfunction "AGND_C1") (pintype "bidirectional"))
      (node (ref "IC9") (pin "C2") (pinfunction "PGND_1_C2") (pintype "bidirectional"))
      (node (ref "IC9") (pin "C3") (pinfunction "PGND_2_C3") (pintype "bidirectional"))
      (node (ref "J1") (pin "17") (pinfunction "17_17") (pintype "bidirectional"))
      (node (ref "J1") (pin "8") (pinfunction "8_8") (pintype "bidirectional"))
      (node (ref "J1") (pin "MP1") (pinfunction "MP1_MP1") (pintype "bidirectional"))
      (node (ref "J1") (pin "MP2") (pinfunction "MP2_MP2") (pintype "bidirectional"))
      (node (ref "J2") (pin "3") (pinfunction "3_3") (pintype "bidirectional"))
      (node (ref "J2") (pin "5") (pinfunction "5_5") (pintype "bidirectional"))
      (node (ref "J4") (pin "A12_B1") (pinfunction "GND_A12_B1") (pintype "power_in"))
      (node (ref "J4") (pin "A1_B12") (pinfunction "GND_A1_B12") (pintype "power_in"))
      (node (ref "J4") (pin "SH1") (pinfunction "SHIELD_SH1") (pintype "passive"))
      (node (ref "J4") (pin "SH2") (pinfunction "SHIELD_SH2") (pintype "passive"))
      (node (ref "J4") (pin "SH3") (pinfunction "SHIELD_SH3") (pintype "passive"))
      (node (ref "J4") (pin "SH4") (pinfunction "SHIELD_SH4") (pintype "passive"))
      (node (ref "R1_USB") (pin "1") (pinfunction "1_1") (pintype "bidirectional"))
      (node (ref "R2_EP_DR") (pin "1") (pinfunction "1_1") (pintype "bidirectional"))
      (node (ref "R2_USB") (pin "2") (pinfunction "2_2") (pintype "bidirectional"))
      (node (ref "R3") (pin "1") (pinfunction "1_1") (pintype "bidirectional"))
      (node (ref "R9") (pin "1") (pinfunction "1_1") (pintype "bidirectional"))
      (node (ref "R_TYPE_SEL") (pin "1") (pinfunction "1_1") (pintype "bidirectional"))
      (node (ref "SJ1") (pin "1") (pinfunction "1_1") (pintype "passive"))
      (node (ref "SW_DN") (pin "1") (pinfunction "1_1") (pintype "passive"))
      (node (ref "SW_ENT") (pin "1") (pinfunction "1_1") (pintype "passive"))
      (node (ref "SW_UP") (pin "1") (pinfunction "1_1") (pintype "passive"))
      (node (ref "TP_BAT_GND") (pin "TP") (pinfunction "TP_TP") (pintype "input"))
      (node (ref "TP_GND") (pin "TP") (pinfunction "TP_TP") (pintype "input"))
      (node (ref "U1") (pin "P$74") (pinfunction "VSS_PAD_P$74") (pintype "bidirectional"))
      (node (ref "U1") (pin "P$75") (pinfunction "VSS_PAD_P$75") (pintype "bidirectional"))
      (node (ref "U1") (pin "P$76") (pinfunction "VSS_PAD_P$76") (pintype "bidirectional"))
      (node (ref "U1") (pin "P$77") (pinfunction "VSS_PAD_P$77") (pintype "bidirectional"))
      (node (ref "U1") (pin "P$78") (pinfunction "VSS_PAD_P$78") (pintype "bidirectional"))
      (node (ref "U1") (pin "P$79") (pinfunction "VSS_PAD_P$79") (pintype "bidirectional"))
      (node (ref "U1") (pin "P$80") (pinfunction "VSS_PAD_P$80") (pintype "bidirectional"))
      (node (ref "U1") (pin "P$81") (pinfunction "VSS_PAD_P$81") (pintype "bidirectional"))
      (node (ref "U1") (pin "P$82") (pinfunction "VSS_PAD_P$82") (pintype "bidirectional"))
      (node (ref "U1") (pin "P$83") (pinfunction "VSS_PAD_P$83") (pintype "bidirectional"))
      (node (ref "U1") (pin "P$84") (pinfunction "VSS_PAD_P$84") (pintype "bidirectional"))
      (node (ref "U1") (pin "P$85") (pinfunction "VSS_PAD_P$85") (pintype "bidirectional"))
      (node (ref "U1") (pin "P$86") (pinfunction "VSS_PAD_P$86") (pintype "bidirectional"))
      (node (ref "U1") (pin "P$87") (pinfunction "VSS_PAD_P$87") (pintype "bidirectional"))
      (node (ref "U1") (pin "P$88") (pinfunction "VSS_PAD_P$88") (pintype "bidirectional"))
      (node (ref "U1") (pin "P$89") (pinfunction "VSS_PAD_P$89") (pintype "bidirectional"))
      (node (ref "U1") (pin "P$90") (pinfunction "VSS_PAD_P$90") (pintype "bidirectional"))
      (node (ref "U1") (pin "P$B7") (pinfunction "VSS_P$B7") (pintype "power_in"))
      (node (ref "U1") (pin "P$F23") (pinfunction "VSS_PA_P$F23") (pintype "bidirectional"))
      (node (ref "U3") (pin "1") (pinfunction "CTG_1") (pintype "power_in"))
      (node (ref "U3") (pin "4") (pinfunction "GND_4") (pintype "power_in"))
      (node (ref "U3") (pin "6") (pinfunction "QSTRT_6") (pintype "input"))
      (node (ref "U3") (pin "9") (pinfunction "EP_9") (pintype "power_in"))
      (node (ref "X1") (pin "2") (pinfunction "2_2") (pintype "passive"))
      (node (ref "X1") (pin "4") (pinfunction "4_4") (pintype "passive"))
    )
    (net (code "17") (name "HAPTIC_EN") (class "Default")
      (node (ref "IC2") (pin "A1") (pinfunction "EN_A1") (pintype "bidirectional"))
      (node (ref "U1") (pin "P$U1") (pinfunction "P0.12_P$U1") (pintype "bidirectional"))
    )
    (net (code "18") (name "IMU_INT1") (class "Default")
      (node (ref "IC3") (pin "5") (pinfunction "INT1_5") (pintype "bidirectional"))
      (node (ref "U1") (pin "P$N1") (pinfunction "P0.08_P$N1") (pintype "bidirectional"))
    )
    (net (code "19") (name "IMU_INT2") (class "Default")
      (node (ref "IC3") (pin "6") (pinfunction "INT2_6") (pintype "bidirectional"))
      (node (ref "U1") (pin "P$P2") (pinfunction "P1.08_P$P2") (pintype "bidirectional"))
    )
    (net (code "20") (name "LX1") (class "Default")
      (node (ref "IC9") (pin "B2") (pinfunction "SW1_1_B2") (pintype "bidirectional"))
      (node (ref "IC9") (pin "B3") (pinfunction "SW1_2_B3") (pintype "bidirectional"))
      (node (ref "L7") (pin "1") (pinfunction "1_1") (pintype "bidirectional"))
    )
    (net (code "21") (name "LX2") (class "Default")
      (node (ref "IC9") (pin "D2") (pinfunction "SW2_1_D2") (pintype "bidirectional"))
      (node (ref "IC9") (pin "D3") (pinfunction "SW2_2_D3") (pintype "bidirectional"))
      (node (ref "L7") (pin "2") (pinfunction "2_2") (pintype "bidirectional"))
    )
    (net (code "22") (name "MOSI") (class "Default")
      (node (ref "J1") (pin "14") (pinfunction "14_14") (pintype "bidirectional"))
      (node (ref "U1") (pin "P$B13") (pinfunction "P0.03/AIN1_P$B13") (pintype "bidirectional"))
    )
    (net (code "23") (name "Net-(ANT1-FEED)") (class "Default")
      (node (ref "ANT1") (pin "1") (pinfunction "FEED_1") (pintype "input"))
      (node (ref "C22") (pin "1") (pinfunction "1_1") (pintype "passive"))
      (node (ref "C4") (pin "1") (pinfunction "1_1") (pintype "passive"))
      (node (ref "L1") (pin "2") (pinfunction "2_2") (pintype "passive"))
    )
    (net (code "24") (name "Net-(D2-K)") (class "Default")
      (node (ref "C2-EP-DR") (pin "1") (pinfunction "1_1") (pintype "passive"))
      (node (ref "D2") (pin "1") (pinfunction "K_1") (pintype "bidirectional"))
      (node (ref "D4") (pin "2") (pinfunction "A_2") (pintype "bidirectional"))
      (node (ref "Q3") (pin "3") (pinfunction "D_3") (pintype "bidirectional"))
    )
    (net (code "25") (name "Net-(D5-A)") (class "Default")
      (node (ref "C2-EP-DR") (pin "2") (pinfunction "2_2") (pintype "passive"))
      (node (ref "D5") (pin "2") (pinfunction "A_2") (pintype "bidirectional"))
      (node (ref "L5") (pin "2") (pinfunction "2_2") (pintype "passive"))
    )
    (net (code "26") (name "Net-(EPD_C1-Pad1)") (class "Default")
      (node (ref "EPD_C1") (pin "1") (pinfunction "1_1") (pintype "passive"))
      (node (ref "J1") (pin "5") (pinfunction "5_5") (pintype "bidirectional"))
    )
    (net (code "27") (name "Net-(EPD_C2-Pad1)") (class "Default")
      (node (ref "EPD_C2") (pin "1") (pinfunction "1_1") (pintype "passive"))
      (node (ref "J1") (pin "4") (pinfunction "4_4") (pintype "bidirectional"))
    )
    (net (code "28") (name "Net-(EPD_C6-Pad1)") (class "Default")
      (node (ref "EPD_C6") (pin "1") (pinfunction "1_1") (pintype "passive"))
      (node (ref "J1") (pin "18") (pinfunction "18_18") (pintype "bidirectional"))
    )
    (net (code "29") (name "Net-(EPD_C7-Pad1)") (class "Default")
      (node (ref "EPD_C7") (pin "1") (pinfunction "1_1") (pintype "passive"))
      (node (ref "J1") (pin "19") (pinfunction "19_19") (pintype "bidirectional"))
    )
    (net (code "30") (name "Net-(EPD_C8-Pad1)") (class "Default")
      (node (ref "EPD_C8") (pin "1") (pinfunction "1_1") (pintype "passive"))
      (node (ref "J1") (pin "20") (pinfunction "20_20") (pintype "bidirectional"))
    )
    (net (code "31") (name "Net-(EPD_C10-Pad1)") (class "Default")
      (node (ref "EPD_C10") (pin "1") (pinfunction "1_1") (pintype "passive"))
      (node (ref "J1") (pin "22") (pinfunction "22_22") (pintype "bidirectional"))
    )
    (net (code "32") (name "Net-(EPD_C12-Pad1)") (class "Default")
      (node (ref "EPD_C12") (pin "1") (pinfunction "1_1") (pintype "passive"))
      (node (ref "J1") (pin "24") (pinfunction "24_24") (pintype "bidirectional"))
    )
    (net (code "33") (name "Net-(IC1-TS{slash}MR)") (class "Default")
      (node (ref "IC1") (pin "D1") (pinfunction "TS/MR_D1") (pintype "bidirectional"))
      (node (ref "R9") (pin "2") (pinfunction "2_2") (pintype "bidirectional"))
    )
    (net (code "34") (name "Net-(IC2-REG)") (class "Default")
      (node (ref "C32") (pin "1") (pinfunction "1_1") (pintype "passive"))
      (node (ref "IC2") (pin "A2") (pinfunction "REG_A2") (pintype "bidirectional"))
    )
    (net (code "35") (name "Net-(IC3-SDO)") (class "Default")
      (node (ref "IC3") (pin "1") (pinfunction "SDO_1") (pintype "bidirectional"))
      (node (ref "R3") (pin "2") (pinfunction "2_2") (pintype "bidirectional"))
    )
    (net (code "36") (name "Net-(IC9-SCL)") (class "Default")
      (node (ref "IC9") (pin "D1") (pinfunction "SCL_D1") (pintype "bidirectional"))
      (node (ref "R4") (pin "2") (pinfunction "2_2") (pintype "bidirectional"))
    )
    (net (code "37") (name "Net-(IC9-SDA)") (class "Default")
      (node (ref "IC9") (pin "E1") (pinfunction "SDA_E1") (pintype "bidirectional"))
      (node (ref "R2") (pin "2") (pinfunction "2_2") (pintype "bidirectional"))
    )
    (net (code "38") (name "Net-(J4-CC1)") (class "Default")
      (node (ref "J4") (pin "A5") (pinfunction "CC1_A5") (pintype "bidirectional"))
      (node (ref "R1_USB") (pin "2") (pinfunction "2_2") (pintype "bidirectional"))
    )
    (net (code "39") (name "Net-(J4-CC2)") (class "Default")
      (node (ref "J4") (pin "B5") (pinfunction "CC2_B5") (pintype "bidirectional"))
      (node (ref "R2_USB") (pin "1") (pinfunction "1_1") (pintype "bidirectional"))
    )
    (net (code "40") (name "Net-(L2-Pad2)") (class "Default")
      (node (ref "L2") (pin "2") (pinfunction "2_2") (pintype "passive"))
      (node (ref "L3") (pin "1") (pinfunction "1_1") (pintype "passive"))
    )
    (net (code "41") (name "Net-(R1_EP_DR-Pad1)") (class "Default")
      (node (ref "R1_EP_DR") (pin "1") (pinfunction "1_1") (pintype "bidirectional"))
      (node (ref "R_TYPE_SEL") (pin "2") (pinfunction "2_2") (pintype "bidirectional"))
      (node (ref "SJ1") (pin "2") (pinfunction "2_2") (pintype "passive"))
    )
    (net (code "42") (name "Net-(U1-ANT)") (class "Default")
      (node (ref "C3") (pin "1") (pinfunction "1_1") (pintype "passive"))
      (node (ref "L1") (pin "1") (pinfunction "1_1") (pintype "passive"))
      (node (ref "U1") (pin "P$H23") (pinfunction "ANT_P$H23") (pintype "bidirectional"))
    )
    (net (code "43") (name "Net-(U1-DCC)") (class "Default")
      (node (ref "L2") (pin "1") (pinfunction "1_1") (pintype "passive"))
      (node (ref "U1") (pin "P$B3") (pinfunction "DCC_P$B3") (pintype "output"))
    )
    (net (code "44") (name "Net-(U1-DEC2)") (class "Default")
      (node (ref "C13") (pin "1") (pinfunction "1_1") (pintype "passive"))
      (node (ref "U1") (pin "P$A18") (pinfunction "DEC2_P$A18") (pintype "bidirectional"))
    )
    (net (code "45") (name "Net-(U1-DEC3V3)") (class "Default")
      (node (ref "C20") (pin "1") (pinfunction "1_1") (pintype "passive"))
      (node (ref "U1") (pin "P$AC5") (pinfunction "DEC3V3_P$AC5") (pintype "bidirectional"))
    )
    (net (code "46") (name "Net-(U1-DEC5)") (class "Default")
      (node (ref "C9") (pin "1") (pinfunction "1_1") (pintype "passive"))
      (node (ref "U1") (pin "P$N24") (pinfunction "DEC5_P$N24") (pintype "bidirectional"))
    )
    (net (code "47") (name "Net-(U1-XC1)") (class "Default")
      (node (ref "C1") (pin "1") (pinfunction "1_1") (pintype "passive"))
      (node (ref "U1") (pin "P$B24") (pinfunction "XC1_P$B24") (pintype "input"))
      (node (ref "X1") (pin "1") (pinfunction "1_1") (pintype "passive"))
    )
    (net (code "48") (name "Net-(U1-XC2)") (class "Default")
      (node (ref "C2") (pin "1") (pinfunction "1_1") (pintype "passive"))
      (node (ref "U1") (pin "P$A23") (pinfunction "XC2_P$A23") (pintype "output"))
      (node (ref "X1") (pin "3") (pinfunction "3_3") (pintype "passive"))
    )
    (net (code "49") (name "OUT+") (class "Default")
      (node (ref "IC2") (pin "A3") (pinfunction "OUT+_A3") (pintype "bidirectional"))
      (node (ref "TP_OP") (pin "TP") (pinfunction "TP_TP") (pintype "input"))
    )
    (net (code "50") (name "OUT-") (class "Default")
      (node (ref "IC2") (pin "C3") (pinfunction "OUT-_C3") (pintype "bidirectional"))
      (node (ref "TP_ON") (pin "TP") (pinfunction "TP_TP") (pintype "input"))
    )
    (net (code "51") (name "P0.00") (class "Default")
      (node (ref "C17") (pin "2") (pinfunction "2_2") (pintype "passive"))
      (node (ref "U1") (pin "P$D2") (pinfunction "P0.00/XL1_P$D2") (pintype "bidirectional"))
      (node (ref "X2") (pin "2") (pinfunction "2_2") (pintype "passive"))
    )
    (net (code "52") (name "P0.01") (class "Default")
      (node (ref "C18") (pin "2") (pinfunction "2_2") (pintype "passive"))
      (node (ref "U1") (pin "P$F2") (pinfunction "P0.01/XL2_P$F2") (pintype "bidirectional"))
      (node (ref "X2") (pin "1") (pinfunction "1_1") (pintype "passive"))
    )
    (net (code "53") (name "P0.04") (class "Default")
      (node (ref "U1") (pin "P$J1") (pinfunction "P0.04/AIN2_P$J1") (pintype "bidirectional"))
    )
    (net (code "54") (name "P0.09") (class "Default")
      (node (ref "U1") (pin "P$L24") (pinfunction "P0.09/NFC1_P$L24") (pintype "bidirectional"))
    )
    (net (code "55") (name "P0.13") (class "Default")
      (node (ref "C30") (pin "2") (pinfunction "2_2") (pintype "passive"))
      (node (ref "R5") (pin "1") (pinfunction "1_1") (pintype "bidirectional"))
      (node (ref "SW_UP") (pin "2") (pinfunction "2_2") (pintype "passive"))
      (node (ref "U1") (pin "P$AD8") (pinfunction "P0.13_P$AD8") (pintype "bidirectional"))
    )
    (net (code "56") (name "P0.14") (class "Default")
      (node (ref "C31") (pin "2") (pinfunction "2_2") (pintype "passive"))
      (node (ref "R8") (pin "1") (pinfunction "1_1") (pintype "bidirectional"))
      (node (ref "SW_ENT") (pin "2") (pinfunction "2_2") (pintype "passive"))
      (node (ref "U1") (pin "P$AC9") (pinfunction "P0.14_P$AC9") (pintype "bidirectional"))
    )
    (net (code "57") (name "P0.19") (class "Default")
      (node (ref "U1") (pin "P$AC15") (pinfunction "P0.19_P$AC15") (pintype "bidirectional"))
    )
    (net (code "58") (name "P0.20") (class "Default")
      (node (ref "U1") (pin "P$AD16") (pinfunction "P0.20_P$AD16") (pintype "bidirectional"))
    )
    (net (code "59") (name "P0.21") (class "Default")
      (node (ref "U1") (pin "P$AC17") (pinfunction "P0.21_P$AC17") (pintype "bidirectional"))
    )
    (net (code "60") (name "P0.22") (class "Default")
      (node (ref "U1") (pin "P$AD18") (pinfunction "P0.22_P$AD18") (pintype "bidirectional"))
    )
    (net (code "61") (name "P0.23") (class "Default")
      (node (ref "U1") (pin "P$AC19") (pinfunction "P0.23_P$AC19") (pintype "bidirectional"))
    )
    (net (code "62") (name "P0.24") (class "Default")
      (node (ref "U1") (pin "P$AD20") (pinfunction "P0.24_P$AD20") (pintype "bidirectional"))
    )
    (net (code "63") (name "P0.25") (class "Default")
      (node (ref "U1") (pin "P$AC21") (pinfunction "P0.25_P$AC21") (pintype "bidirectional"))
    )
    (net (code "64") (name "P0.26") (class "Default")
      (node (ref "U1") (pin "P$G1") (pinfunction "P0.26_P$G1") (pintype "bidirectional"))
    )
    (net (code "65") (name "P0.27") (class "Default")
      (node (ref "U1") (pin "P$H2") (pinfunction "P0.27_P$H2") (pintype "bidirectional"))
    )
    (net (code "66") (name "P0.28") (class "Default")
      (node (ref "U1") (pin "P$B11") (pinfunction "P0.28/AIN4_P$B11") (pintype "bidirectional"))
    )
    (net (code "67") (name "P0.29") (class "Default")
      (node (ref "U1") (pin "P$A10") (pinfunction "P0.29/AIN5_P$A10") (pintype "bidirectional"))
    )
    (net (code "68") (name "P0.30") (class "Default")
      (node (ref "U1") (pin "P$B9") (pinfunction "P0.30/AIN6_P$B9") (pintype "bidirectional"))
    )
    (net (code "69") (name "P0.31") (class "Default")
      (node (ref "U1") (pin "P$A8") (pinfunction "P0.31/AIN7_P$A8") (pintype "bidirectional"))
    )
    (net (code "70") (name "P1.01") (class "Default")
      (node (ref "Q1") (pin "1") (pinfunction "G_1") (pintype "bidirectional"))
      (node (ref "R_PWR_EPD") (pin "1") (pinfunction "1_1") (pintype "bidirectional"))
      (node (ref "U1") (pin "P$Y23") (pinfunction "P1.01_P$Y23") (pintype "bidirectional"))
    )
    (net (code "71") (name "P1.02") (class "Default")
      (node (ref "C29") (pin "2") (pinfunction "2_2") (pintype "passive"))
      (node (ref "R7") (pin "1") (pinfunction "1_1") (pintype "bidirectional"))
      (node (ref "SW_DN") (pin "2") (pinfunction "2_2") (pintype "passive"))
      (node (ref "U1") (pin "P$W24") (pinfunction "P1.02_P$W24") (pintype "bidirectional"))
    )
    (net (code "72") (name "P1.03") (class "Default")
      (node (ref "U1") (pin "P$V23") (pinfunction "P1.03_P$V23") (pintype "bidirectional"))
    )
    (net (code "73") (name "P1.04") (class "Default")
      (node (ref "U1") (pin "P$U24") (pinfunction "P1.04_P$U24") (pintype "bidirectional"))
    )
    (net (code "74") (name "P1.05") (class "Default")
      (node (ref "U1") (pin "P$T23") (pinfunction "P1.05_P$T23") (pintype "bidirectional"))
    )
    (net (code "75") (name "P1.06") (class "Default")
      (node (ref "U1") (pin "P$R24") (pinfunction "P1.06_P$R24") (pintype "bidirectional"))
    )
    (net (code "76") (name "P1.07") (class "Default")
      (node (ref "U1") (pin "P$P23") (pinfunction "P1.07_P$P23") (pintype "bidirectional"))
    )
    (net (code "77") (name "P1.09") (class "Default")
      (node (ref "U1") (pin "P$R1") (pinfunction "P1.09_P$R1") (pintype "bidirectional"))
    )
    (net (code "78") (name "P1.10") (class "Default")
      (node (ref "U1") (pin "P$A20") (pinfunction "P1.10_P$A20") (pintype "bidirectional"))
    )
    (net (code "79") (name "P1.11") (class "Default")
      (node (ref "U1") (pin "P$B19") (pinfunction "P1.11_P$B19") (pintype "bidirectional"))
    )
    (net (code "80") (name "P1.12") (class "Default")
      (node (ref "U1") (pin "P$B17") (pinfunction "P1.12_P$B17") (pintype "bidirectional"))
    )
    (net (code "81") (name "P1.13") (class "Default")
      (node (ref "U1") (pin "P$A16") (pinfunction "P1.13_P$A16") (pintype "bidirectional"))
    )
    (net (code "82") (name "P1.14") (class "Default")
      (node (ref "U1") (pin "P$B15") (pinfunction "P1.14_P$B15") (pintype "bidirectional"))
    )
    (net (code "83") (name "P1.15") (class "Default")
      (node (ref "U1") (pin "P$A14") (pinfunction "P1.15_P$A14") (pintype "bidirectional"))
    )
    (net (code "84") (name "PMIC_INT") (class "Default")
      (node (ref "IC1") (pin "A1") (pinfunction "~{INT}_A1") (pintype "bidirectional"))
      (node (ref "U1") (pin "P$T2") (pinfunction "P0.11_P$T2") (pintype "bidirectional"))
    )
    (net (code "85") (name "PREVGH") (class "Default")
      (node (ref "D5") (pin "1") (pinfunction "K_1") (pintype "bidirectional"))
      (node (ref "EPD_C9") (pin "1") (pinfunction "1_1") (pintype "passive"))
      (node (ref "J1") (pin "21") (pinfunction "21_21") (pintype "bidirectional"))
    )
    (net (code "86") (name "PREVGL") (class "Default")
      (node (ref "D2") (pin "2") (pinfunction "A_2") (pintype "bidirectional"))
      (node (ref "EPD_C11") (pin "1") (pinfunction "1_1") (pintype "passive"))
      (node (ref "J1") (pin "23") (pinfunction "23_23") (pintype "bidirectional"))
    )
    (net (code "87") (name "RESE") (class "Default")
      (node (ref "J1") (pin "3") (pinfunction "3_3") (pintype "bidirectional"))
      (node (ref "Q3") (pin "2") (pinfunction "S_2") (pintype "bidirectional"))
      (node (ref "R1_EP_DR") (pin "2") (pinfunction "2_2") (pintype "bidirectional"))
    )
    (net (code "88") (name "RESET") (class "Default")
      (node (ref "J2") (pin "6") (pinfunction "6_6") (pintype "bidirectional"))
      (node (ref "TP_RESET") (pin "TP") (pinfunction "TP_TP") (pintype "input"))
      (node (ref "U1") (pin "P$AC13") (pinfunction "P0.18/RESET_P$AC13") (pintype "bidirectional"))
    )
    (net (code "89") (name "SCK") (class "Default")
      (node (ref "J1") (pin "13") (pinfunction "13_13") (pintype "bidirectional"))
      (node (ref "U1") (pin "P$A12") (pinfunction "P0.02/AIN0_P$A12") (pintype "bidirectional"))
    )
    (net (code "90") (name "SCL") (class "Default")
      (node (ref "IC1") (pin "B1") (pinfunction "SCL_B1") (pintype "bidirectional"))
      (node (ref "IC2") (pin "C1") (pinfunction "SCL_C1") (pintype "bidirectional"))
      (node (ref "IC3") (pin "12") (pinfunction "SCX_12") (pintype "bidirectional"))
      (node (ref "R17") (pin "2") (pinfunction "2_2") (pintype "bidirectional"))
      (node (ref "R4") (pin "1") (pinfunction "1_1") (pintype "bidirectional"))
      (node (ref "TP_SCL") (pin "TP") (pinfunction "TP_TP") (pintype "input"))
      (node (ref "U1") (pin "P$M2") (pinfunction "P0.07_P$M2") (pintype "bidirectional"))
      (node (ref "U3") (pin "7") (pinfunction "SCL_7") (pintype "input"))
    )
    (net (code "91") (name "SDA") (class "Default")
      (node (ref "IC1") (pin "C1") (pinfunction "SDA_C1") (pintype "bidirectional"))
      (node (ref "IC2") (pin "B2") (pinfunction "SDA_B2") (pintype "bidirectional"))
      (node (ref "IC3") (pin "2") (pinfunction "SDX_2") (pintype "bidirectional"))
      (node (ref "R18") (pin "2") (pinfunction "2_2") (pintype "bidirectional"))
      (node (ref "R2") (pin "1") (pinfunction "1_1") (pintype "bidirectional"))
      (node (ref "TP_SDA") (pin "TP") (pinfunction "TP_TP") (pintype "input"))
      (node (ref "U1") (pin "P$L1") (pinfunction "P0.06_P$L1") (pintype "bidirectional"))
      (node (ref "U3") (pin "8") (pinfunction "SDA_8") (pintype "bidirectional"))
    )
    (net (code "92") (name "SWDCLK") (class "Default")
      (node (ref "J2") (pin "4") (pinfunction "4_4") (pintype "bidirectional"))
      (node (ref "TP_SWDCLK") (pin "TP") (pinfunction "TP_TP") (pintype "input"))
      (node (ref "U1") (pin "P$AA24") (pinfunction "SWDCLK_P$AA24") (pintype "input"))
    )
    (net (code "93") (name "SWDIO") (class "Default")
      (node (ref "J2") (pin "2") (pinfunction "2_2") (pintype "bidirectional"))
      (node (ref "TP_SWDIO") (pin "TP") (pinfunction "TP_TP") (pintype "input"))
      (node (ref "U1") (pin "P$AC24") (pinfunction "SWDIO_P$AC24") (pintype "bidirectional"))
    )
    (net (code "94") (name "SWO") (class "Default")
      (node (ref "TP_SWO") (pin "TP") (pinfunction "TP_TP") (pintype "input"))
      (node (ref "U1") (pin "P$AD22") (pinfunction "P1.00_P$AD22") (pintype "bidirectional"))
    )
    (net (code "95") (name "VBAT") (class "Default")
      (node (ref "C27") (pin "2") (pinfunction "2_2") (pintype "passive"))
      (node (ref "C37") (pin "2") (pinfunction "2_2") (pintype "passive"))
      (node (ref "IC1") (pin "C2") (pinfunction "BAT_C2") (pintype "bidirectional"))
      (node (ref "TP_VBAT") (pin "TP") (pinfunction "TP_TP") (pintype "input"))
      (node (ref "U3") (pin "2") (pinfunction "CELL_2") (pintype "power_in"))
      (node (ref "U3") (pin "3") (pinfunction "VDD_3") (pintype "power_in"))
    )
    (net (code "96") (name "VBUS") (class "Default")
      (node (ref "C21") (pin "1") (pinfunction "1_1") (pintype "passive"))
      (node (ref "C38") (pin "2") (pinfunction "2_2") (pintype "passive"))
      (node (ref "C42") (pin "1") (pinfunction "1_1") (pintype "passive"))
      (node (ref "C43") (pin "1") (pinfunction "1_1") (pintype "passive"))
      (node (ref "D3") (pin "5") (pinfunction "VBUS_5") (pintype "bidirectional"))
      (node (ref "IC1") (pin "A2") (pinfunction "IN_A2") (pintype "bidirectional"))
      (node (ref "J4") (pin "A4_B9") (pinfunction "VBUS_A4_B9") (pintype "power_in"))
      (node (ref "J4") (pin "A9_B4") (pinfunction "VBUS_A9_B4") (pintype "power_in"))
      (node (ref "U1") (pin "P$AD2") (pinfunction "VBUS_P$AD2") (pintype "power_in"))
    )
    (net (code "97") (name "VREG") (class "Default")
      (node (ref "C23") (pin "2") (pinfunction "2_2") (pintype "passive"))
      (node (ref "C24") (pin "2") (pinfunction "2_2") (pintype "passive"))
      (node (ref "C39") (pin "1") (pinfunction "1_1") (pintype "passive"))
      (node (ref "IC1") (pin "B2") (pinfunction "SYS_B2") (pintype "bidirectional"))
      (node (ref "IC9") (pin "A1") (pinfunction "EN_A1") (pintype "bidirectional"))
      (node (ref "IC9") (pin "A2") (pinfunction "VIN_1_A2") (pintype "bidirectional"))
      (node (ref "IC9") (pin "A3") (pinfunction "VIN_2_A3") (pintype "bidirectional"))
      (node (ref "TP_VREG") (pin "TP") (pinfunction "TP_TP") (pintype "input"))
    )
    (net (code "98") (name "unconnected-(ANT1-NC-Pad2)") (class "Default")
      (node (ref "ANT1") (pin "2") (pinfunction "NC_2") (pintype "no_connect"))
    )
    (net (code "99") (name "unconnected-(IC3-ASCL-Pad11)") (class "Default")
      (node (ref "IC3") (pin "11") (pinfunction "ASCL_11") (pintype "bidirectional"))
    )
    (net (code "100") (name "unconnected-(IC3-ASDA-Pad4)") (class "Default")
      (node (ref "IC3") (pin "4") (pinfunction "ASDA_4") (pintype "bidirectional"))
    )
    (net (code "101") (name "unconnected-(J1-Pad1)") (class "Default")
      (node (ref "J1") (pin "1") (pinfunction "1_1") (pintype "bidirectional"))
    )
    (net (code "102") (name "unconnected-(J1-Pad6)") (class "Default")
      (node (ref "J1") (pin "6") (pinfunction "6_6") (pintype "bidirectional"))
    )
    (net (code "103") (name "unconnected-(J1-Pad7)") (class "Default")
      (node (ref "J1") (pin "7") (pinfunction "7_7") (pintype "bidirectional"))
    )
    (net (code "104") (name "unconnected-(J4-SBU1-PadA8)") (class "Default")
      (node (ref "J4") (pin "A8") (pinfunction "SBU1_A8") (pintype "bidirectional"))
    )
    (net (code "105") (name "unconnected-(J4-SBU2-PadB8)") (class "Default")
      (node (ref "J4") (pin "B8") (pinfunction "SBU2_B8") (pintype "bidirectional"))
    )
    (net (code "106") (name "unconnected-(U1-DCCH-PadP$AB2)") (class "Default")
      (node (ref "U1") (pin "P$AB2") (pinfunction "DCCH_P$AB2") (pintype "bidirectional"))
    )
  )
)
